# PLD_RadFET_Differential_Lowpass.net
KiCad netlist of a schematic drawn in Altium Designer
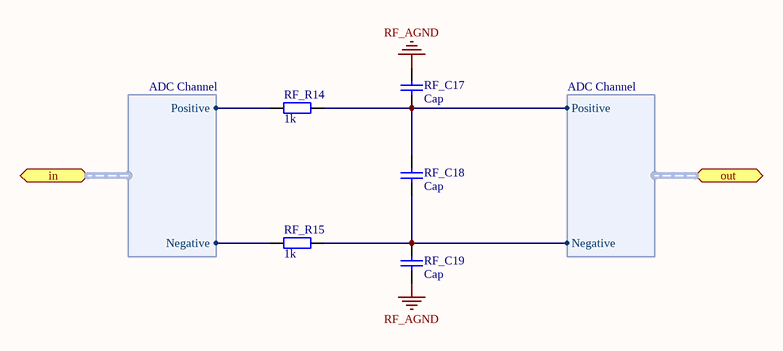
[diagram p0: PLD_RadFET_Differential_Lowpass.SchDoc]

(export (version "E")
  (design (tool "Eeschema 10.0.6"))
  (components
    (comp (ref "RF_C17")
      (value "Cap")
      (footprint "SMD_Capacitor_0603")
      (libsource (lib "capacitors") (part "Cap"))
    )
    (comp (ref "RF_C18")
      (value "Cap")
      (footprint "SMD_Capacitor_0603")
      (libsource (lib "capacitors") (part "Cap"))
    )
    (comp (ref "RF_C19")
      (value "Cap")
      (footprint "SMD_Capacitor_0603")
      (libsource (lib "capacitors") (part "Cap"))
    )
    (comp (ref "RF_R14")
      (value "1k")
      (footprint "SMD_Resistor_0603")
      (libsource (lib "resistors") (part "Res"))
    )
    (comp (ref "RF_R15")
      (value "1k")
      (footprint "SMD_Resistor_0603")
      (libsource (lib "resistors") (part "Res"))
    )
  )
  (nets
    (net (code "4") (name "Net-(RF_C17-Pad2)") (class "Default")
      (node (ref "RF_C17") (pin "2") (pinfunction "2_2") (pintype "passive"))
      (node (ref "RF_C18") (pin "1") (pinfunction "1_1") (pintype "passive"))
      (node (ref "RF_R14") (pin "2") (pinfunction "2_2") (pintype "passive"))
    )
    (net (code "5") (name "Net-(RF_C18-Pad2)") (class "Default")
      (node (ref "RF_C18") (pin "2") (pinfunction "2_2") (pintype "passive"))
      (node (ref "RF_C19") (pin "1") (pinfunction "1_1") (pintype "passive"))
      (node (ref "RF_R15") (pin "2") (pinfunction "2_2") (pintype "passive"))
    )
    (net (code "6") (name "RF_AGND") (class "Default")
      (node (ref "RF_C17") (pin "1") (pinfunction "1_1") (pintype "passive"))
      (node (ref "RF_C19") (pin "2") (pinfunction "2_2") (pintype "passive"))
    )
    (net (code "7") (name "unconnected-(RF_R14-Pad1)") (class "Default")
      (node (ref "RF_R14") (pin "1") (pinfunction "1_1") (pintype "passive"))
    )
    (net (code "8") (name "unconnected-(RF_R15-Pad1)") (class "Default")
      (node (ref "RF_R15") (pin "1") (pinfunction "1_1") (pintype "passive"))
    )
  )
)
